# Shield_robottino_schem.net
KiCad netlist of a schematic drawn in Altium Designer
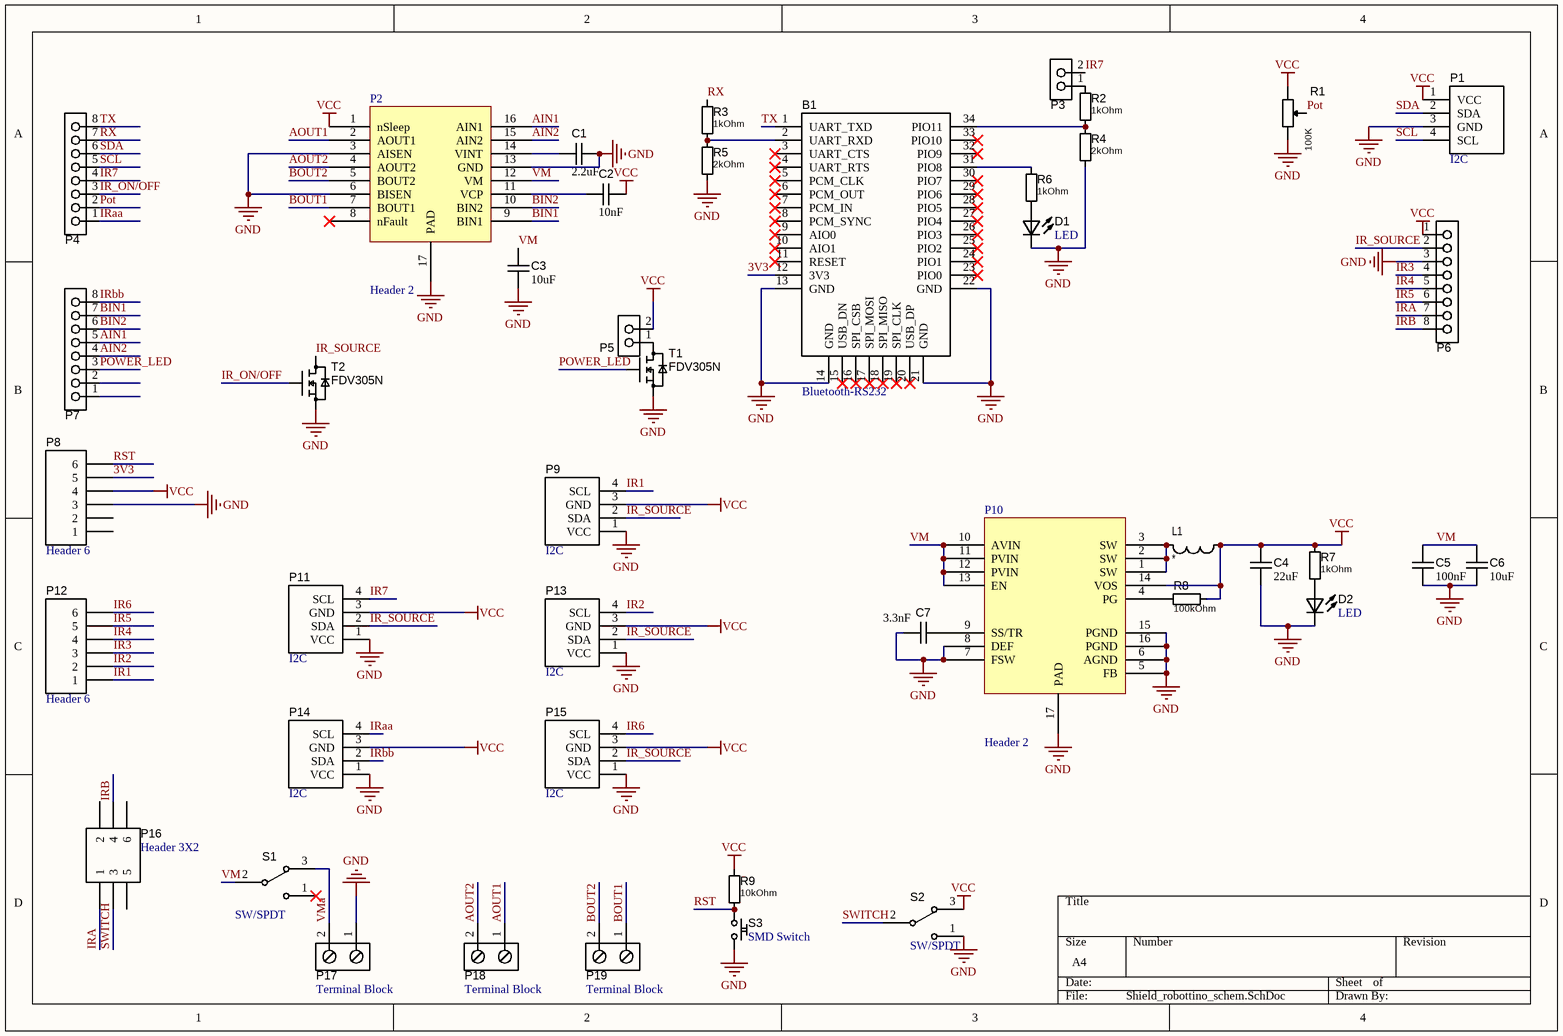
[diagram p0: Shield_robottino_schem.SchDoc]

(export (version "E")
  (design (tool "Eeschema 10.0.6"))
  (components
    (comp (ref "B1")
      (value "Bluetooth-RS232")
      (footprint "Bluetooth_PRismino")
      (description "Bluetooth to RS232 Module")
      (libsource (lib "andylib") (part "Bluetooth-RS232"))
    )
    (comp (ref "C1")
      (value "2.2uF")
      (footprint "C/0805")
      (description "Capacitor")
      (fields (field (name "Comment") "C1") (field (name "PUBLISHER") "Altium Limited"))
      (libsource (lib "andylib") (part "C"))
    )
    (comp (ref "C2")
      (value "10nF")
      (footprint "C/0805")
      (description "Capacitor")
      (fields (field (name "Comment") "C2") (field (name "PUBLISHER") "Altium Limited"))
      (libsource (lib "andylib") (part "C"))
    )
    (comp (ref "C3")
      (value "10uF")
      (footprint "C/0805")
      (description "Capacitor")
      (fields (field (name "Comment") "C3") (field (name "PUBLISHER") "Altium Limited"))
      (libsource (lib "andylib") (part "C"))
    )
    (comp (ref "C4")
      (value "22uF")
      (footprint "C/0805")
      (description "Capacitor")
      (fields (field (name "Comment") "C4") (field (name "PUBLISHER") "Altium Limited"))
      (libsource (lib "andylib") (part "C"))
    )
    (comp (ref "C5")
      (value "100nF")
      (footprint "C/0805")
      (description "Capacitor")
      (fields (field (name "Comment") "C6") (field (name "PUBLISHER") "Altium Limited"))
      (libsource (lib "andylib") (part "C"))
    )
    (comp (ref "C6")
      (value "10uF")
      (footprint "C/0805")
      (description "Capacitor")
      (fields (field (name "Comment") "C7") (field (name "PUBLISHER") "Altium Limited"))
      (libsource (lib "andylib") (part "C"))
    )
    (comp (ref "C7")
      (value "3.3nF")
      (footprint "C/0805")
      (description "Capacitor")
      (fields (field (name "Comment") "C5") (field (name "PUBLISHER") "Altium Limited"))
      (libsource (lib "andylib") (part "C"))
    )
    (comp (ref "D1")
      (value "LED")
      (footprint "LED-2012[0805]")
      (fields (field (name "PUBLISHER") "Altium Limited"))
      (libsource (lib "andylib") (part "LED"))
    )
    (comp (ref "D2")
      (value "LED")
      (footprint "LED-2012[0805]")
      (fields (field (name "PUBLISHER") "Altium Limited"))
      (libsource (lib "andylib") (part "LED"))
    )
    (comp (ref "L1") (value "*") (footprint "RL622-2R2K-RC") (libsource (lib "andylib") (part "L")))
    (comp (ref "P1")
      (value "I2C")
      (footprint "TYCO/215079-4")
      (description "Micromatch I2C Connector")
      (libsource (lib "") (part "Micromatch-I2C_1"))
    )
    (comp (ref "P2")
      (value "Header 2")
      (footprint "DRV8833PWPR")
      (description "Header, 2-Pin")
      (fields (field (name "PUBLISHER") "Altium Limited"))
      (libsource (lib "marcolib") (part "DRV8833PWPR"))
    )
    (comp (ref "P3")
      (value "Header 2")
      (footprint "HEADER1x2")
      (description "Header, 2-Pin")
      (fields (field (name "PUBLISHER") "Altium Limited"))
      (libsource (lib "andylib") (part "Header 2"))
    )
    (comp (ref "P4")
      (value "Header 8")
      (footprint "Arduino Pad 8")
      (description "Header, 8-Pin")
      (fields (field (name "PUBLISHER") "Altium Limited"))
      (libsource (lib "") (part "Header 8_1"))
    )
    (comp (ref "P5")
      (value "Header 2")
      (footprint "HEADER1x2")
      (description "Header, 2-Pin")
      (fields (field (name "PUBLISHER") "Altium Limited"))
      (libsource (lib "andylib") (part "Header 2"))
    )
    (comp (ref "P6")
      (value "Header 8")
      (footprint "TYCO/215079-8")
      (description "Header, 8-Pin")
      (fields (field (name "PUBLISHER") "Altium Limited"))
      (libsource (lib "andylib") (part "Header 8"))
    )
    (comp (ref "P7")
      (value "Header 8")
      (footprint "Arduino Pad 8")
      (description "Header, 8-Pin")
      (fields (field (name "PUBLISHER") "Altium Limited"))
      (libsource (lib "") (part "Header 8_1"))
    )
    (comp (ref "P8")
      (value "Header 6")
      (footprint "Arduino Pad 6")
      (description "Header, 6-Pin")
      (fields (field (name "PUBLISHER") "Altium Limited"))
      (libsource (lib "andylib") (part "Header 6"))
    )
    (comp (ref "P9")
      (value "I2C")
      (footprint "TYCO/215079-4")
      (description "Micromatch I2C Connector")
      (libsource (lib "andylib") (part "Micromatch-I2C"))
    )
    (comp (ref "P10")
      (value "Header 2")
      (footprint "TPS62133 - duplicate")
      (description "Header, 2-Pin")
      (fields (field (name "PUBLISHER") "Altium Limited"))
      (libsource (lib "marcolib") (part "TPS62133"))
    )
    (comp (ref "P11")
      (value "I2C")
      (footprint "TYCO/215079-4")
      (description "Micromatch I2C Connector")
      (libsource (lib "andylib") (part "Micromatch-I2C"))
    )
    (comp (ref "P12")
      (value "Header 6")
      (footprint "Arduino Pad 6")
      (description "Header, 6-Pin")
      (fields (field (name "PUBLISHER") "Altium Limited"))
      (libsource (lib "andylib") (part "Header 6"))
    )
    (comp (ref "P13")
      (value "I2C")
      (footprint "TYCO/215079-4")
      (description "Micromatch I2C Connector")
      (libsource (lib "andylib") (part "Micromatch-I2C"))
    )
    (comp (ref "P14")
      (value "I2C")
      (footprint "TYCO/215079-4")
      (description "Micromatch I2C Connector")
      (libsource (lib "andylib") (part "Micromatch-I2C"))
    )
    (comp (ref "P15")
      (value "I2C")
      (footprint "TYCO/215079-4")
      (description "Micromatch I2C Connector")
      (libsource (lib "andylib") (part "Micromatch-I2C"))
    )
    (comp (ref "P16")
      (value "Header 3X2")
      (footprint "HEADER2X3")
      (description "Header, 3-Pin, Dual row")
      (fields (field (name "PUBLISHER") "Altium Limited"))
      (libsource (lib "andylib") (part "Header 3X2"))
    )
    (comp (ref "P17")
      (value "Terminal Block")
      (footprint "Phoenix PT 2-Pole")
      (description "2-Pin Screw Terminal")
      (fields (field (name "PUBLISHER") "Altium Limited"))
      (libsource (lib "andylib") (part "Screw Block 2"))
    )
    (comp (ref "P18")
      (value "Terminal Block")
      (footprint "Phoenix PT 2-Pole")
      (description "2-Pin Screw Terminal")
      (fields (field (name "PUBLISHER") "Altium Limited"))
      (libsource (lib "andylib") (part "Screw Block 2"))
    )
    (comp (ref "P19")
      (value "Terminal Block")
      (footprint "Phoenix PT 2-Pole")
      (description "2-Pin Screw Terminal")
      (fields (field (name "PUBLISHER") "Altium Limited"))
      (libsource (lib "andylib") (part "Screw Block 2"))
    )
    (comp (ref "R1")
      (value "100K")
      (footprint "POT/Bourns-3362P")
      (description "Potentiometer")
      (fields (field (name "Comment") "POT_Bourns") (field (name "PUBLISHER") "Altium Limited"))
      (libsource (lib "andylib") (part "POT_Bourns"))
    )
    (comp (ref "R2")
      (value "1kOhm")
      (footprint "R/0805")
      (description "Resistor")
      (fields (field (name "PUBLISHER") "Altium Limited"))
      (libsource (lib "andylib") (part "R"))
    )
    (comp (ref "R3")
      (value "1kOhm")
      (footprint "R/0805")
      (description "Resistor")
      (fields (field (name "PUBLISHER") "Altium Limited"))
      (libsource (lib "andylib") (part "R"))
    )
    (comp (ref "R4")
      (value "2kOhm")
      (footprint "R/0805")
      (description "Resistor")
      (fields (field (name "PUBLISHER") "Altium Limited"))
      (libsource (lib "andylib") (part "R"))
    )
    (comp (ref "R5")
      (value "2kOhm")
      (footprint "R/0805")
      (description "Resistor")
      (fields (field (name "PUBLISHER") "Altium Limited"))
      (libsource (lib "andylib") (part "R"))
    )
    (comp (ref "R6")
      (value "1kOhm")
      (footprint "R/0805")
      (description "Resistor")
      (fields (field (name "PUBLISHER") "Altium Limited"))
      (libsource (lib "andylib") (part "R"))
    )
    (comp (ref "R7")
      (value "1kOhm")
      (footprint "R/0805")
      (description "Resistor")
      (fields (field (name "PUBLISHER") "Altium Limited"))
      (libsource (lib "andylib") (part "R"))
    )
    (comp (ref "R8")
      (value "100kOhm")
      (footprint "R/0805")
      (description "Resistor")
      (fields (field (name "PUBLISHER") "Altium Limited"))
      (libsource (lib "") (part "R_1"))
    )
    (comp (ref "R9")
      (value "10kOhm")
      (footprint "R/0805")
      (description "Resistor")
      (fields (field (name "PUBLISHER") "Altium Limited"))
      (libsource (lib "andylib") (part "R"))
    )
    (comp (ref "S1")
      (value "SW/SPDT")
      (footprint "SW/OS-SPDT")
      (description "SPDT Subminiature Toggle Switch, Right Angle Mounting, Vertical Actuation")
      (fields (field (name "PUBLISHER") "Altium Limited"))
      (libsource (lib "andylib") (part "SW-SPDT"))
    )
    (comp (ref "S2")
      (value "SW/SPDT")
      (footprint "SW/OS-SPDT")
      (description "SPDT Subminiature Toggle Switch, Right Angle Mounting, Vertical Actuation")
      (fields (field (name "PUBLISHER") "Altium Limited"))
      (libsource (lib "andylib") (part "SW-SPDT"))
    )
    (comp (ref "S3")
      (value "SMD Switch")
      (footprint "SMD_SW_Red")
      (description "Switch")
      (fields (field (name "PUBLISHER") "Altium Limited"))
      (libsource (lib "andylib") (part "SMD Switch"))
    )
    (comp (ref "T1")
      (value "FDV305N")
      (footprint "SOT23-3")
      (description "MOSFET N SOT-23 20V 220mOhm")
      (libsource (lib "andylib") (part "T/FDV305N"))
    )
    (comp (ref "T2")
      (value "FDV305N")
      (footprint "SOT23-3")
      (description "MOSFET N SOT-23 20V 220mOhm")
      (libsource (lib "andylib") (part "T/FDV305N"))
    )
  )
  (nets
    (net (code "1") (name "/3V3") (class "Default")
      (node (ref "B1") (pin "12") (pinfunction "3V3_12") (pintype "passive"))
      (node (ref "P8") (pin "5") (pinfunction "5_5") (pintype "passive"))
    )
    (net (code "2") (name "/AIN1") (class "Default")
      (node (ref "P2") (pin "16") (pinfunction "AIN1_16") (pintype "passive"))
      (node (ref "P7") (pin "5") (pinfunction "5_5") (pintype "passive"))
    )
    (net (code "3") (name "/AIN2") (class "Default")
      (node (ref "P2") (pin "15") (pinfunction "AIN2_15") (pintype "passive"))
      (node (ref "P7") (pin "4") (pinfunction "4_4") (pintype "passive"))
    )
    (net (code "4") (name "/AOUT1") (class "Default")
      (node (ref "P18") (pin "1") (pinfunction "1_1") (pintype "passive"))
      (node (ref "P2") (pin "2") (pinfunction "AOUT1_2") (pintype "passive"))
    )
    (net (code "5") (name "/AOUT2") (class "Default")
      (node (ref "P18") (pin "2") (pinfunction "2_2") (pintype "passive"))
      (node (ref "P2") (pin "4") (pinfunction "AOUT2_4") (pintype "passive"))
    )
    (net (code "6") (name "/BIN1") (class "Default")
      (node (ref "P2") (pin "9") (pinfunction "BIN1_9") (pintype "passive"))
      (node (ref "P7") (pin "7") (pinfunction "7_7") (pintype "passive"))
    )
    (net (code "7") (name "/BIN2") (class "Default")
      (node (ref "P2") (pin "10") (pinfunction "BIN2_10") (pintype "passive"))
      (node (ref "P7") (pin "6") (pinfunction "6_6") (pintype "passive"))
    )
    (net (code "8") (name "/BOUT1") (class "Default")
      (node (ref "P19") (pin "1") (pinfunction "1_1") (pintype "passive"))
      (node (ref "P2") (pin "7") (pinfunction "BOUT1_7") (pintype "passive"))
    )
    (net (code "9") (name "/BOUT2") (class "Default")
      (node (ref "P19") (pin "2") (pinfunction "2_2") (pintype "passive"))
      (node (ref "P2") (pin "5") (pinfunction "BOUT2_5") (pintype "passive"))
    )
    (net (code "10") (name "/IR1") (class "Default")
      (node (ref "P12") (pin "1") (pinfunction "1_1") (pintype "passive"))
      (node (ref "P9") (pin "4") (pinfunction "SCL_4") (pintype "passive"))
    )
    (net (code "11") (name "/IR2") (class "Default")
      (node (ref "P12") (pin "2") (pinfunction "2_2") (pintype "passive"))
      (node (ref "P13") (pin "4") (pinfunction "SCL_4") (pintype "passive"))
    )
    (net (code "12") (name "/IR3") (class "Default")
      (node (ref "P12") (pin "3") (pinfunction "3_3") (pintype "passive"))
      (node (ref "P6") (pin "4") (pinfunction "4_4") (pintype "passive"))
    )
    (net (code "13") (name "/IR4") (class "Default")
      (node (ref "P12") (pin "4") (pinfunction "4_4") (pintype "passive"))
      (node (ref "P6") (pin "5") (pinfunction "5_5") (pintype "passive"))
    )
    (net (code "14") (name "/IR5") (class "Default")
      (node (ref "P12") (pin "5") (pinfunction "5_5") (pintype "passive"))
      (node (ref "P6") (pin "6") (pinfunction "6_6") (pintype "passive"))
    )
    (net (code "15") (name "/IR6") (class "Default")
      (node (ref "P12") (pin "6") (pinfunction "6_6") (pintype "passive"))
      (node (ref "P15") (pin "4") (pinfunction "SCL_4") (pintype "passive"))
    )
    (net (code "16") (name "/IR7") (class "Default")
      (node (ref "P11") (pin "4") (pinfunction "SCL_4") (pintype "passive"))
      (node (ref "P3") (pin "2") (pinfunction "2_2") (pintype "passive"))
      (node (ref "P4") (pin "4") (pinfunction "4_4") (pintype "passive"))
    )
    (net (code "17") (name "/IRA") (class "Default")
      (node (ref "P16") (pin "1") (pinfunction "1_1") (pintype "passive"))
      (node (ref "P6") (pin "7") (pinfunction "7_7") (pintype "passive"))
    )
    (net (code "18") (name "/IRB") (class "Default")
      (node (ref "P16") (pin "4") (pinfunction "4_4") (pintype "passive"))
      (node (ref "P6") (pin "8") (pinfunction "8_8") (pintype "passive"))
    )
    (net (code "19") (name "/IR_ON{slash}OFF") (class "Default")
      (node (ref "P4") (pin "3") (pinfunction "3_3") (pintype "passive"))
      (node (ref "T2") (pin "1") (pinfunction "G_1") (pintype "passive"))
    )
    (net (code "20") (name "/IR_SOURCE") (class "Default")
      (node (ref "P11") (pin "2") (pinfunction "SDA_2") (pintype "passive"))
      (node (ref "P13") (pin "2") (pinfunction "SDA_2") (pintype "passive"))
      (node (ref "P15") (pin "2") (pinfunction "SDA_2") (pintype "passive"))
      (node (ref "P6") (pin "2") (pinfunction "2_2") (pintype "passive"))
      (node (ref "P9") (pin "2") (pinfunction "SDA_2") (pintype "passive"))
      (node (ref "T2") (pin "3") (pinfunction "D_3") (pintype "passive"))
    )
    (net (code "21") (name "/IRaa") (class "Default")
      (node (ref "P14") (pin "4") (pinfunction "SCL_4") (pintype "passive"))
      (node (ref "P4") (pin "1") (pinfunction "1_1") (pintype "passive"))
    )
    (net (code "22") (name "/IRbb") (class "Default")
      (node (ref "P14") (pin "2") (pinfunction "SDA_2") (pintype "passive"))
      (node (ref "P7") (pin "8") (pinfunction "8_8") (pintype "passive"))
    )
    (net (code "23") (name "/POWER_LED") (class "Default")
      (node (ref "P7") (pin "3") (pinfunction "3_3") (pintype "passive"))
      (node (ref "T1") (pin "1") (pinfunction "G_1") (pintype "passive"))
    )
    (net (code "24") (name "/Pot") (class "Default")
      (node (ref "P4") (pin "2") (pinfunction "2_2") (pintype "passive"))
      (node (ref "R1") (pin "2") (pinfunction "2_2") (pintype "passive"))
    )
    (net (code "25") (name "/RST") (class "Default")
      (node (ref "P8") (pin "6") (pinfunction "6_6") (pintype "passive"))
      (node (ref "R9") (pin "1") (pinfunction "1_1") (pintype "passive"))
      (node (ref "S3") (pin "1") (pinfunction "1_1") (pintype "passive"))
    )
    (net (code "26") (name "/RX") (class "Default")
      (node (ref "P4") (pin "7") (pinfunction "7_7") (pintype "passive"))
      (node (ref "R3") (pin "2") (pinfunction "2_2") (pintype "passive"))
    )
    (net (code "27") (name "/SCL") (class "Default")
      (node (ref "P1") (pin "4") (pinfunction "SCL_4") (pintype "passive"))
      (node (ref "P4") (pin "5") (pinfunction "5_5") (pintype "passive"))
    )
    (net (code "28") (name "/SDA") (class "Default")
      (node (ref "P1") (pin "2") (pinfunction "SDA_2") (pintype "passive"))
      (node (ref "P4") (pin "6") (pinfunction "6_6") (pintype "passive"))
    )
    (net (code "29") (name "/SWITCH") (class "Default")
      (node (ref "P16") (pin "3") (pinfunction "3_3") (pintype "passive"))
      (node (ref "S2") (pin "2") (pinfunction "2_2") (pintype "passive"))
    )
    (net (code "30") (name "/TX") (class "Default")
      (node (ref "B1") (pin "1") (pinfunction "UART_TXD_1") (pintype "passive"))
      (node (ref "P4") (pin "8") (pinfunction "8_8") (pintype "passive"))
    )
    (net (code "31") (name "/VM") (class "Default")
      (node (ref "C3") (pin "2") (pinfunction "2_2") (pintype "passive"))
      (node (ref "C5") (pin "2") (pinfunction "2_2") (pintype "passive"))
      (node (ref "C6") (pin "2") (pinfunction "2_2") (pintype "passive"))
      (node (ref "P10") (pin "10") (pinfunction "AVIN_10") (pintype "passive"))
      (node (ref "P10") (pin "11") (pinfunction "PVIN_11") (pintype "passive"))
      (node (ref "P10") (pin "12") (pinfunction "PVIN_12") (pintype "passive"))
      (node (ref "P10") (pin "13") (pinfunction "EN_13") (pintype "passive"))
      (node (ref "P2") (pin "12") (pinfunction "VM_12") (pintype "passive"))
      (node (ref "S1") (pin "2") (pinfunction "2_2") (pintype "passive"))
    )
    (net (code "32") (name "/VMa") (class "Default")
      (node (ref "P17") (pin "2") (pinfunction "2_2") (pintype "passive"))
      (node (ref "S1") (pin "3") (pinfunction "3_3") (pintype "passive"))
    )
    (net (code "33") (name "GND") (class "Default")
      (node (ref "B1") (pin "13") (pinfunction "GND_13") (pintype "passive"))
      (node (ref "B1") (pin "14") (pinfunction "GND_14") (pintype "passive"))
      (node (ref "B1") (pin "21") (pinfunction "GND_21") (pintype "passive"))
      (node (ref "B1") (pin "22") (pinfunction "GND_22") (pintype "passive"))
      (node (ref "C1") (pin "2") (pinfunction "2_2") (pintype "passive"))
      (node (ref "C3") (pin "1") (pinfunction "1_1") (pintype "passive"))
      (node (ref "C4") (pin "1") (pinfunction "1_1") (pintype "passive"))
      (node (ref "C5") (pin "1") (pinfunction "1_1") (pintype "passive"))
      (node (ref "C6") (pin "1") (pinfunction "1_1") (pintype "passive"))
      (node (ref "C7") (pin "1") (pinfunction "1_1") (pintype "passive"))
      (node (ref "D1") (pin "K") (pinfunction "K_K") (pintype "passive"))
      (node (ref "D2") (pin "K") (pinfunction "K_K") (pintype "passive"))
      (node (ref "P1") (pin "3") (pinfunction "GND_3") (pintype "passive"))
      (node (ref "P10") (pin "15") (pinfunction "PGND_15") (pintype "passive"))
      (node (ref "P10") (pin "16") (pinfunction "PGND_16") (pintype "passive"))
      (node (ref "P10") (pin "17") (pinfunction "PAD_17") (pintype "passive"))
      (node (ref "P10") (pin "5") (pinfunction "FB_5") (pintype "passive"))
      (node (ref "P10") (pin "6") (pinfunction "AGND_6") (pintype "passive"))
      (node (ref "P10") (pin "7") (pinfunction "FSW_7") (pintype "passive"))
      (node (ref "P10") (pin "8") (pinfunction "DEF_8") (pintype "passive"))
      (node (ref "P11") (pin "1") (pinfunction "VCC_1") (pintype "passive"))
      (node (ref "P13") (pin "1") (pinfunction "VCC_1") (pintype "passive"))
      (node (ref "P14") (pin "1") (pinfunction "VCC_1") (pintype "passive"))
      (node (ref "P15") (pin "1") (pinfunction "VCC_1") (pintype "passive"))
      (node (ref "P17") (pin "1") (pinfunction "1_1") (pintype "passive"))
      (node (ref "P2") (pin "13") (pinfunction "GND_13") (pintype "passive"))
      (node (ref "P2") (pin "17") (pinfunction "PAD_17") (pintype "passive"))
      (node (ref "P2") (pin "3") (pinfunction "AISEN_3") (pintype "passive"))
      (node (ref "P2") (pin "6") (pinfunction "BISEN_6") (pintype "passive"))
      (node (ref "P6") (pin "3") (pinfunction "3_3") (pintype "passive"))
      (node (ref "P8") (pin "3") (pinfunction "3_3") (pintype "passive"))
      (node (ref "P9") (pin "1") (pinfunction "VCC_1") (pintype "passive"))
      (node (ref "R1") (pin "3") (pinfunction "3_3") (pintype "passive"))
      (node (ref "R4") (pin "1") (pinfunction "1_1") (pintype "passive"))
      (node (ref "R5") (pin "1") (pinfunction "1_1") (pintype "passive"))
      (node (ref "S2") (pin "1") (pinfunction "1_1") (pintype "passive"))
      (node (ref "S3") (pin "2") (pinfunction "2_2") (pintype "passive"))
      (node (ref "T1") (pin "2") (pinfunction "S_2") (pintype "passive"))
      (node (ref "T2") (pin "2") (pinfunction "S_2") (pintype "passive"))
    )
    (net (code "34") (name "Net-(B1-PIO8)") (class "Default")
      (node (ref "B1") (pin "31") (pinfunction "PIO8_31") (pintype "passive"))
      (node (ref "R6") (pin "2") (pinfunction "2_2") (pintype "passive"))
    )
    (net (code "35") (name "Net-(B1-PIO11)") (class "Default")
      (node (ref "B1") (pin "34") (pinfunction "PIO11_34") (pintype "passive"))
      (node (ref "R2") (pin "1") (pinfunction "1_1") (pintype "passive"))
      (node (ref "R4") (pin "2") (pinfunction "2_2") (pintype "passive"))
    )
    (net (code "36") (name "Net-(B1-UART_RXD)") (class "Default")
      (node (ref "B1") (pin "2") (pinfunction "UART_RXD_2") (pintype "passive"))
      (node (ref "R3") (pin "1") (pinfunction "1_1") (pintype "passive"))
      (node (ref "R5") (pin "2") (pinfunction "2_2") (pintype "passive"))
    )
    (net (code "37") (name "Net-(D1-PadA)") (class "Default")
      (node (ref "D1") (pin "A") (pinfunction "A_A") (pintype "passive"))
      (node (ref "R6") (pin "1") (pinfunction "1_1") (pintype "passive"))
    )
    (net (code "38") (name "Net-(D2-PadA)") (class "Default")
      (node (ref "D2") (pin "A") (pinfunction "A_A") (pintype "passive"))
      (node (ref "R7") (pin "1") (pinfunction "1_1") (pintype "passive"))
    )
    (net (code "39") (name "Net-(L1-Pad1)") (class "Default")
      (node (ref "L1") (pin "1") (pintype "passive"))
      (node (ref "P10") (pin "1") (pinfunction "SW_1") (pintype "passive"))
      (node (ref "P10") (pin "2") (pinfunction "SW_2") (pintype "passive"))
      (node (ref "P10") (pin "3") (pinfunction "SW_3") (pintype "passive"))
    )
    (net (code "40") (name "Net-(P2-VCP)") (class "Default")
      (node (ref "C2") (pin "1") (pinfunction "1_1") (pintype "passive"))
      (node (ref "P2") (pin "11") (pinfunction "VCP_11") (pintype "passive"))
    )
    (net (code "41") (name "Net-(P2-VINT)") (class "Default")
      (node (ref "C1") (pin "1") (pinfunction "1_1") (pintype "passive"))
      (node (ref "P2") (pin "14") (pinfunction "VINT_14") (pintype "passive"))
    )
    (net (code "42") (name "Net-(P3-Pad1)") (class "Default")
      (node (ref "P3") (pin "1") (pinfunction "1_1") (pintype "passive"))
      (node (ref "R2") (pin "2") (pinfunction "2_2") (pintype "passive"))
    )
    (net (code "43") (name "Net-(P10-PG)") (class "Default")
      (node (ref "P10") (pin "4") (pinfunction "PG_4") (pintype "passive"))
      (node (ref "R8") (pin "1") (pinfunction "1_1") (pintype "passive"))
    )
    (net (code "44") (name "Net-(P10-SS{slash}TR)") (class "Default")
      (node (ref "C7") (pin "2") (pinfunction "2_2") (pintype "passive"))
      (node (ref "P10") (pin "9") (pinfunction "SS/TR_9") (pintype "passive"))
    )
    (net (code "45") (name "Net-(T1-D)") (class "Default")
      (node (ref "P5") (pin "1") (pinfunction "1_1") (pintype "passive"))
      (node (ref "T1") (pin "3") (pinfunction "D_3") (pintype "passive"))
    )
    (net (code "46") (name "VCC") (class "Default")
      (node (ref "C2") (pin "2") (pinfunction "2_2") (pintype "passive"))
      (node (ref "C4") (pin "2") (pinfunction "2_2") (pintype "passive"))
      (node (ref "L1") (pin "2") (pintype "passive"))
      (node (ref "P1") (pin "1") (pinfunction "VCC_1") (pintype "passive"))
      (node (ref "P10") (pin "14") (pinfunction "VOS_14") (pintype "passive"))
      (node (ref "P11") (pin "3") (pinfunction "GND_3") (pintype "passive"))
      (node (ref "P13") (pin "3") (pinfunction "GND_3") (pintype "passive"))
      (node (ref "P14") (pin "3") (pinfunction "GND_3") (pintype "passive"))
      (node (ref "P15") (pin "3") (pinfunction "GND_3") (pintype "passive"))
      (node (ref "P2") (pin "1") (pinfunction "nSleep_1") (pintype "passive"))
      (node (ref "P5") (pin "2") (pinfunction "2_2") (pintype "passive"))
      (node (ref "P6") (pin "1") (pinfunction "1_1") (pintype "passive"))
      (node (ref "P8") (pin "4") (pinfunction "4_4") (pintype "passive"))
      (node (ref "P9") (pin "3") (pinfunction "GND_3") (pintype "passive"))
      (node (ref "R1") (pin "1") (pinfunction "1_1") (pintype "passive"))
      (node (ref "R7") (pin "2") (pinfunction "2_2") (pintype "passive"))
      (node (ref "R8") (pin "2") (pinfunction "2_2") (pintype "passive"))
      (node (ref "R9") (pin "2") (pinfunction "2_2") (pintype "passive"))
      (node (ref "S2") (pin "3") (pinfunction "3_3") (pintype "passive"))
    )
    (net (code "47") (name "unconnected-(B1-AIO0-Pad9)") (class "Default")
      (node (ref "B1") (pin "9") (pinfunction "AIO0_9") (pintype "passive+no_connect"))
    )
    (net (code "48") (name "unconnected-(B1-AIO1-Pad10)") (class "Default")
      (node (ref "B1") (pin "10") (pinfunction "AIO1_10") (pintype "passive+no_connect"))
    )
    (net (code "49") (name "unconnected-(B1-PCM_CLK-Pad5)") (class "Default")
      (node (ref "B1") (pin "5") (pinfunction "PCM_CLK_5") (pintype "passive+no_connect"))
    )
    (net (code "50") (name "unconnected-(B1-PCM_IN-Pad7)") (class "Default")
      (node (ref "B1") (pin "7") (pinfunction "PCM_IN_7") (pintype "passive+no_connect"))
    )
    (net (code "51") (name "unconnected-(B1-PCM_OUT-Pad6)") (class "Default")
      (node (ref "B1") (pin "6") (pinfunction "PCM_OUT_6") (pintype "passive+no_connect"))
    )
    (net (code "52") (name "unconnected-(B1-PCM_SYNC-Pad8)") (class "Default")
      (node (ref "B1") (pin "8") (pinfunction "PCM_SYNC_8") (pintype "passive+no_connect"))
    )
    (net (code "53") (name "unconnected-(B1-PIO0-Pad23)") (class "Default")
      (node (ref "B1") (pin "23") (pinfunction "PIO0_23") (pintype "passive+no_connect"))
    )
    (net (code "54") (name "unconnected-(B1-PIO1-Pad24)") (class "Default")
      (node (ref "B1") (pin "24") (pinfunction "PIO1_24") (pintype "passive+no_connect"))
    )
    (net (code "55") (name "unconnected-(B1-PIO2-Pad25)") (class "Default")
      (node (ref "B1") (pin "25") (pinfunction "PIO2_25") (pintype "passive+no_connect"))
    )
    (net (code "56") (name "unconnected-(B1-PIO3-Pad26)") (class "Default")
      (node (ref "B1") (pin "26") (pinfunction "PIO3_26") (pintype "passive+no_connect"))
    )
    (net (code "57") (name "unconnected-(B1-PIO4-Pad27)") (class "Default")
      (node (ref "B1") (pin "27") (pinfunction "PIO4_27") (pintype "passive+no_connect"))
    )
    (net (code "58") (name "unconnected-(B1-PIO5-Pad28)") (class "Default")
      (node (ref "B1") (pin "28") (pinfunction "PIO5_28") (pintype "passive+no_connect"))
    )
    (net (code "59") (name "unconnected-(B1-PIO6-Pad29)") (class "Default")
      (node (ref "B1") (pin "29") (pinfunction "PIO6_29") (pintype "passive+no_connect"))
    )
    (net (code "60") (name "unconnected-(B1-PIO7-Pad30)") (class "Default")
      (node (ref "B1") (pin "30") (pinfunction "PIO7_30") (pintype "passive+no_connect"))
    )
    (net (code "61") (name "unconnected-(B1-PIO9-Pad32)") (class "Default")
      (node (ref "B1") (pin "32") (pinfunction "PIO9_32") (pintype "passive+no_connect"))
    )
    (net (code "62") (name "unconnected-(B1-PIO10-Pad33)") (class "Default")
      (node (ref "B1") (pin "33") (pinfunction "PIO10_33") (pintype "passive+no_connect"))
    )
    (net (code "63") (name "unconnected-(B1-RESET-Pad11)") (class "Default")
      (node (ref "B1") (pin "11") (pinfunction "RESET_11") (pintype "passive+no_connect"))
    )
    (net (code "64") (name "unconnected-(B1-SPI_CLK-Pad19)") (class "Default")
      (node (ref "B1") (pin "19") (pinfunction "SPI_CLK_19") (pintype "passive+no_connect"))
    )
    (net (code "65") (name "unconnected-(B1-SPI_CSB-Pad16)") (class "Default")
      (node (ref "B1") (pin "16") (pinfunction "SPI_CSB_16") (pintype "passive+no_connect"))
    )
    (net (code "66") (name "unconnected-(B1-SPI_MISO-Pad18)") (class "Default")
      (node (ref "B1") (pin "18") (pinfunction "SPI_MISO_18") (pintype "passive+no_connect"))
    )
    (net (code "67") (name "unconnected-(B1-SPI_MOSI-Pad17)") (class "Default")
      (node (ref "B1") (pin "17") (pinfunction "SPI_MOSI_17") (pintype "passive+no_connect"))
    )
    (net (code "68") (name "unconnected-(B1-UART_CTS-Pad3)") (class "Default")
      (node (ref "B1") (pin "3") (pinfunction "UART_CTS_3") (pintype "passive+no_connect"))
    )
    (net (code "69") (name "unconnected-(B1-UART_RTS-Pad4)") (class "Default")
      (node (ref "B1") (pin "4") (pinfunction "UART_RTS_4") (pintype "passive+no_connect"))
    )
    (net (code "70") (name "unconnected-(B1-USB_DN-Pad15)") (class "Default")
      (node (ref "B1") (pin "15") (pinfunction "USB_DN_15") (pintype "passive+no_connect"))
    )
    (net (code "71") (name "unconnected-(B1-USB_DP-Pad20)") (class "Default")
      (node (ref "B1") (pin "20") (pinfunction "USB_DP_20") (pintype "passive+no_connect"))
    )
    (net (code "72") (name "unconnected-(P2-nFault-Pad8)") (class "Default")
      (node (ref "P2") (pin "8") (pinfunction "nFault_8") (pintype "passive+no_connect"))
    )
    (net (code "73") (name "unconnected-(P7-Pad1)") (class "Default")
      (node (ref "P7") (pin "1") (pinfunction "1_1") (pintype "passive"))
    )
    (net (code "74") (name "unconnected-(P7-Pad2)") (class "Default")
      (node (ref "P7") (pin "2") (pinfunction "2_2") (pintype "passive"))
    )
    (net (code "75") (name "unconnected-(P8-Pad1)") (class "Default")
      (node (ref "P8") (pin "1") (pinfunction "1_1") (pintype "passive"))
    )
    (net (code "76") (name "unconnected-(P8-Pad2)") (class "Default")
      (node (ref "P8") (pin "2") (pinfunction "2_2") (pintype "passive"))
    )
    (net (code "77") (name "unconnected-(P16-Pad2)") (class "Default")
      (node (ref "P16") (pin "2") (pinfunction "2_2") (pintype "passive"))
    )
    (net (code "78") (name "unconnected-(P16-Pad5)") (class "Default")
      (node (ref "P16") (pin "5") (pinfunction "5_5") (pintype "passive"))
    )
    (net (code "79") (name "unconnected-(P16-Pad6)") (class "Default")
      (node (ref "P16") (pin "6") (pinfunction "6_6") (pintype "passive"))
    )
    (net (code "80") (name "unconnected-(S1-Pad1)") (class "Default")
      (node (ref "S1") (pin "1") (pinfunction "1_1") (pintype "passive+no_connect"))
    )
  )
)
